# SaidasMotoresCC.net
KiCad netlist of a schematic drawn in Altium Designer
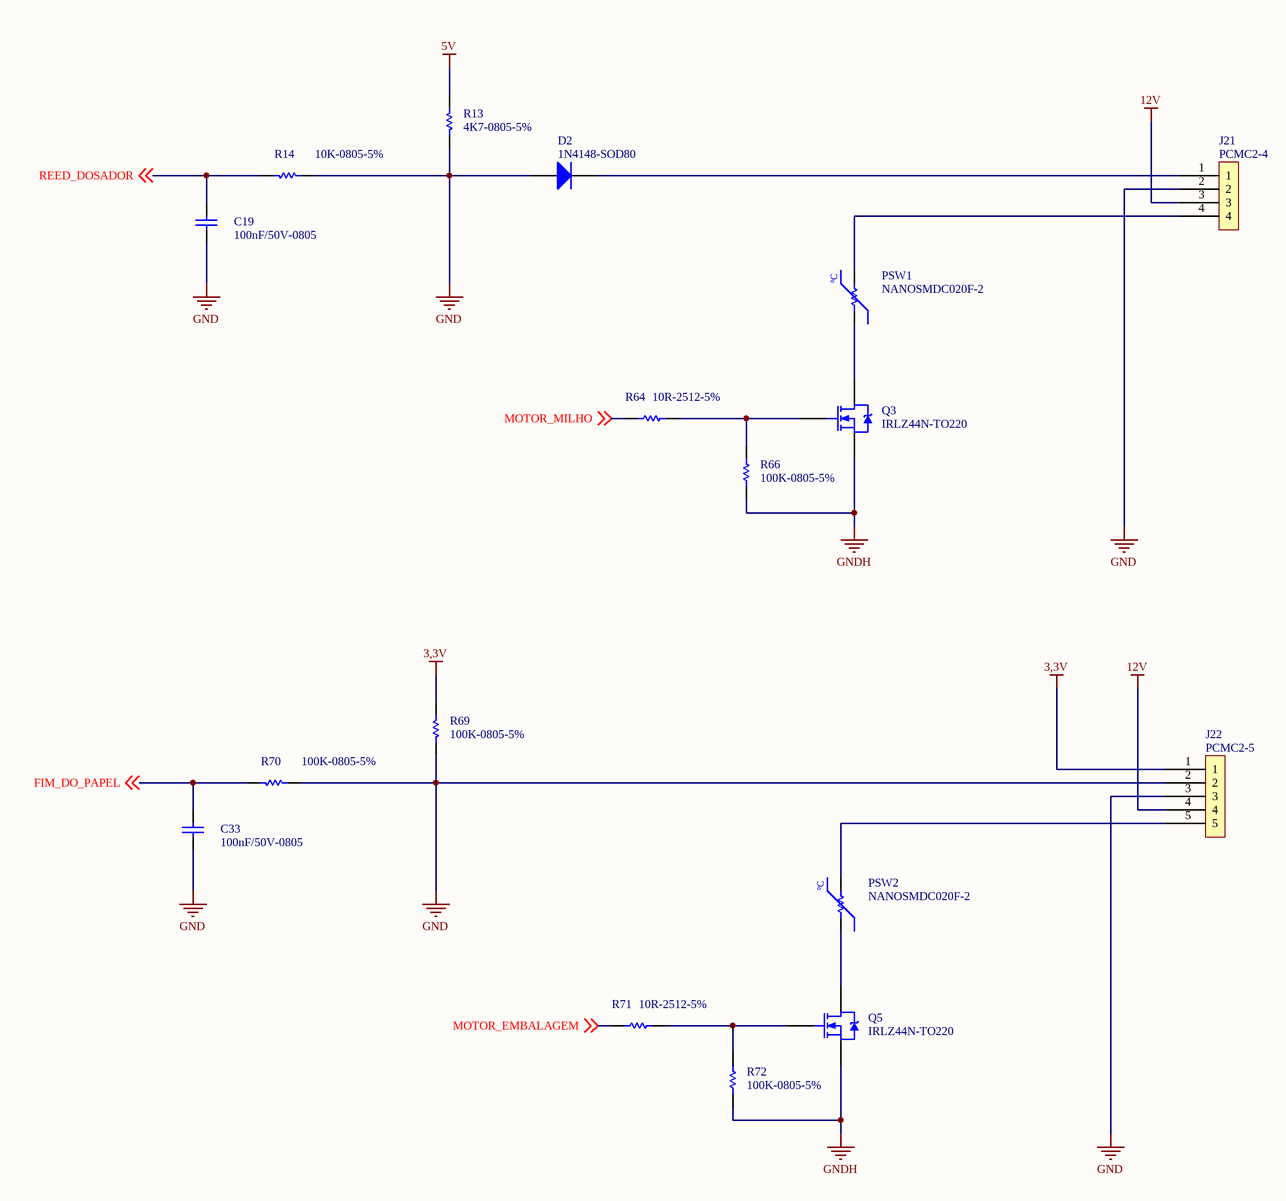
[diagram p0: SaidasMotoresCC.SchDoc]

(export (version "E")
  (design (tool "Eeschema 10.0.6"))
  (components
    (comp (ref "C19")
      (value "100nF/50V-0805")
      (footprint "0805-REVISADO ONDA")
      (description "100nF/50-0805-NPO")
      (libsource (lib "AquinoLib") (part "100nF/50-0805-NPO"))
    )
    (comp (ref "C33")
      (value "100nF/50V-0805")
      (footprint "0805-REVISADO ONDA")
      (description "100nF/50-0805-NPO")
      (libsource (lib "AquinoLib") (part "100nF/50-0805-NPO"))
    )
    (comp (ref "D2") (value "1N4148-SOD80") (libsource (lib "AquinoLib") (part "1N4148-SOD80")))
    (comp (ref "J21") (value "PCMC2-4") (footprint "PCMC2-4") (libsource (lib "AquinoLib") (part "PCMC2-4")))
    (comp (ref "J22") (value "PCMC2-5") (footprint "PCMC2-5") (libsource (lib "AquinoLib") (part "PCMC2-5")))
    (comp (ref "PSW1")
      (value "NANOSMDC020F-2")
      (footprint "2512 - REVISADO ONDA")
      (libsource (lib "AquinoLib") (part "POLYSWITCH 200mA"))
    )
    (comp (ref "PSW2")
      (value "NANOSMDC020F-2")
      (footprint "2512 - REVISADO ONDA")
      (libsource (lib "AquinoLib") (part "POLYSWITCH 200mA"))
    )
    (comp (ref "Q3")
      (value "IRLZ44N-TO220")
      (footprint "TO220-3 EM PÉ")
      (libsource (lib "ChaveDigital3") (part "IRLZ44N-TO220"))
    )
    (comp (ref "Q5")
      (value "IRLZ44N-TO220")
      (footprint "TO220-3 EM PÉ")
      (libsource (lib "ChaveDigital3") (part "IRLZ44N-TO220"))
    )
    (comp (ref "R13")
      (value "4K7-0805-5%")
      (footprint "0805-REVISADO ONDA")
      (description "10K-0805-5%")
      (libsource (lib "AquinoLib") (part "10K-0805-5%"))
    )
    (comp (ref "R14")
      (value "10K-0805-5%")
      (footprint "0805-REVISADO ONDA")
      (description "1K-0805-5%")
      (libsource (lib "AquinoLib") (part "1K-0805-5%"))
    )
    (comp (ref "R64")
      (value "10R-2512-5%")
      (footprint "1206-REVISADO ONDA")
      (description "100K-0805-5%")
      (libsource (lib "AquinoLib") (part "100K-0805-5%"))
    )
    (comp (ref "R66")
      (value "100K-0805-5%")
      (footprint "0805-REVISADO ONDA")
      (libsource (lib "AquinoLib") (part "100K-0805-5%"))
    )
    (comp (ref "R69")
      (value "100K-0805-5%")
      (footprint "0805-REVISADO ONDA")
      (description "10K-0805-5%")
      (libsource (lib "AquinoLib") (part "10K-0805-5%"))
    )
    (comp (ref "R70")
      (value "100K-0805-5%")
      (footprint "0805-REVISADO ONDA")
      (description "1K-0805-5%")
      (libsource (lib "AquinoLib") (part "1K-0805-5%"))
    )
    (comp (ref "R71")
      (value "10R-2512-5%")
      (footprint "1206-REVISADO ONDA")
      (description "100K-0805-5%")
      (libsource (lib "AquinoLib") (part "100K-0805-5%"))
    )
    (comp (ref "R72")
      (value "100K-0805-5%")
      (footprint "0805-REVISADO ONDA")
      (libsource (lib "AquinoLib") (part "100K-0805-5%"))
    )
  )
  (nets
    (net (code "1") (name "3,3V") (class "Default")
      (node (ref "J22") (pin "1") (pinfunction "1_1") (pintype "passive"))
      (node (ref "R69") (pin "2") (pinfunction "2_2") (pintype "passive"))
    )
    (net (code "2") (name "5V") (class "Default")
      (node (ref "R13") (pin "2") (pinfunction "2_2") (pintype "passive"))
    )
    (net (code "3") (name "12V") (class "Default")
      (node (ref "J21") (pin "3") (pinfunction "3_3") (pintype "passive"))
      (node (ref "J22") (pin "4") (pinfunction "4_4") (pintype "passive"))
    )
    (net (code "4") (name "FIM_DO_PAPEL") (class "Default")
      (node (ref "C33") (pin "2") (pinfunction "2_2") (pintype "passive"))
      (node (ref "R70") (pin "2") (pinfunction "2_2") (pintype "passive"))
    )
    (net (code "5") (name "GND") (class "Default")
      (node (ref "C19") (pin "1") (pinfunction "1_1") (pintype "passive"))
      (node (ref "C33") (pin "1") (pinfunction "1_1") (pintype "passive"))
      (node (ref "D2") (pin "1") (pinfunction "1_1") (pintype "passive"))
      (node (ref "J21") (pin "2") (pinfunction "2_2") (pintype "passive"))
      (node (ref "J22") (pin "2") (pinfunction "2_2") (pintype "passive"))
      (node (ref "J22") (pin "3") (pinfunction "3_3") (pintype "passive"))
      (node (ref "R13") (pin "1") (pinfunction "1_1") (pintype "passive"))
      (node (ref "R14") (pin "1") (pinfunction "1_1") (pintype "passive"))
      (node (ref "R69") (pin "1") (pinfunction "1_1") (pintype "passive"))
      (node (ref "R70") (pin "1") (pinfunction "1_1") (pintype "passive"))
    )
    (net (code "6") (name "GNDH") (class "Default")
      (node (ref "Q3") (pin "3") (pinfunction "S_3") (pintype "passive"))
      (node (ref "Q5") (pin "3") (pinfunction "S_3") (pintype "passive"))
      (node (ref "R66") (pin "1") (pinfunction "1_1") (pintype "passive"))
      (node (ref "R72") (pin "1") (pinfunction "1_1") (pintype "passive"))
    )
    (net (code "7") (name "MOTOR_EMBALAGEM") (class "Default")
      (node (ref "R71") (pin "2") (pinfunction "2_2") (pintype "passive"))
    )
    (net (code "8") (name "MOTOR_MILHO") (class "Default")
      (node (ref "R64") (pin "2") (pinfunction "2_2") (pintype "passive"))
    )
    (net (code "9") (name "Net-(D2-Pad2)") (class "Default")
      (node (ref "D2") (pin "2") (pinfunction "2_2") (pintype "passive"))
      (node (ref "J21") (pin "1") (pinfunction "1_1") (pintype "passive"))
    )
    (net (code "10") (name "Net-(J21-Pad4)") (class "Default")
      (node (ref "J21") (pin "4") (pinfunction "4_4") (pintype "passive"))
      (node (ref "PSW1") (pin "2") (pinfunction "2_2") (pintype "passive"))
    )
    (net (code "11") (name "Net-(J22-Pad5)") (class "Default")
      (node (ref "J22") (pin "5") (pinfunction "5_5") (pintype "passive"))
      (node (ref "PSW2") (pin "2") (pinfunction "2_2") (pintype "passive"))
    )
    (net (code "12") (name "Net-(Q3-D)") (class "Default")
      (node (ref "PSW1") (pin "1") (pinfunction "1_1") (pintype "passive"))
      (node (ref "Q3") (pin "2") (pinfunction "D_2") (pintype "passive"))
    )
    (net (code "13") (name "Net-(Q3-G)") (class "Default")
      (node (ref "Q3") (pin "1") (pinfunction "G_1") (pintype "passive"))
      (node (ref "R64") (pin "1") (pinfunction "1_1") (pintype "passive"))
      (node (ref "R66") (pin "2") (pinfunction "2_2") (pintype "passive"))
    )
    (net (code "14") (name "Net-(Q5-D)") (class "Default")
      (node (ref "PSW2") (pin "1") (pinfunction "1_1") (pintype "passive"))
      (node (ref "Q5") (pin "2") (pinfunction "D_2") (pintype "passive"))
    )
    (net (code "15") (name "Net-(Q5-G)") (class "Default")
      (node (ref "Q5") (pin "1") (pinfunction "G_1") (pintype "passive"))
      (node (ref "R71") (pin "1") (pinfunction "1_1") (pintype "passive"))
      (node (ref "R72") (pin "2") (pinfunction "2_2") (pintype "passive"))
    )
    (net (code "16") (name "REED_DOSADOR") (class "Default")
      (node (ref "C19") (pin "2") (pinfunction "2_2") (pintype "passive"))
      (node (ref "R14") (pin "2") (pinfunction "2_2") (pintype "passive"))
    )
  )
)
